# PowerShield.net
KiCad netlist of a schematic drawn in EAGLE
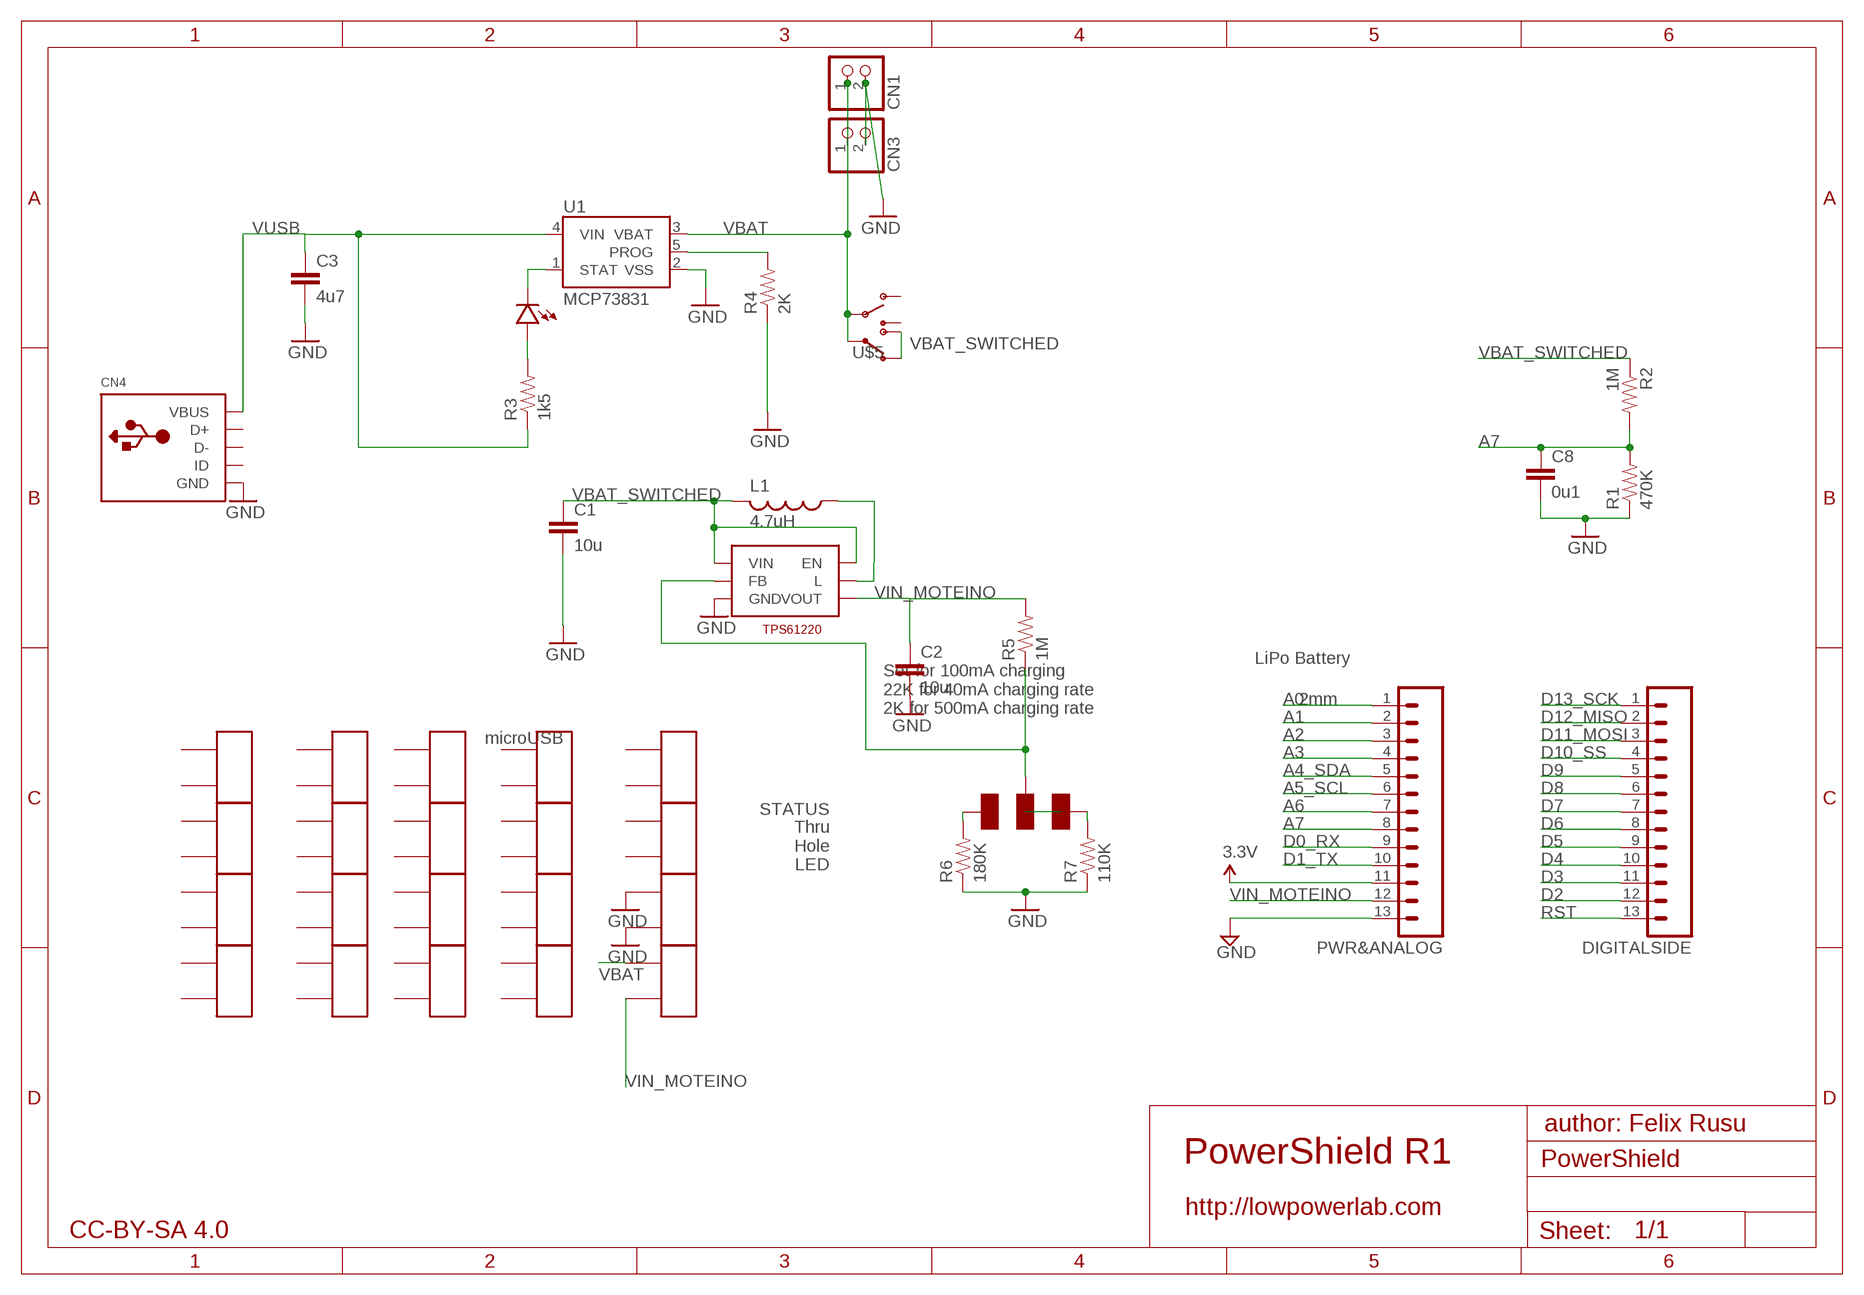
[diagram p0: schematic, sheet 1]

(export (version "E")
  (design (tool "Eeschema 10.0.6"))
  (components
    (comp (ref "C1")
      (value "10u")
      (footprint "eagle-import:0805-CAP-LARGEPADS")
      (libsource (lib "eagle-import") (part "CAP0805-CAP-LARGEPADS"))
    )
    (comp (ref "C2")
      (value "10u")
      (footprint "eagle-import:0805-CAP-LARGEPADS")
      (libsource (lib "eagle-import") (part "CAP0805-CAP-LARGEPADS"))
    )
    (comp (ref "C3")
      (value "4u7")
      (footprint "eagle-import:0603-CAP")
      (libsource (lib "eagle-import") (part "SparkFun_CAP0603-CAP"))
    )
    (comp (ref "C8")
      (value "0u1")
      (footprint "eagle-import:0603-CAP")
      (libsource (lib "eagle-import") (part "CAP0603-CAP"))
    )
    (comp (ref "CN1")
      (value "JST_2PIN-THM-RA")
      (footprint "eagle-import:JST-PH-2-THM-RA")
      (libsource (lib "eagle-import") (part "JST_2PIN-THM-RA"))
    )
    (comp (ref "CN3")
      (value "JST_2PIN-SMT-RA")
      (footprint "eagle-import:JST-PH-2-SMT-RA")
      (libsource (lib "eagle-import") (part "JST_2PIN-SMT-RA"))
    )
    (comp (ref "CN4")
      (value "USBMINIB")
      (footprint "eagle-import:USB-MINIB")
      (libsource (lib "eagle-import") (part "USBMINIB"))
    )
    (comp (ref "DIGITALSIDE")
      (value "HDR_13PINREGULAR")
      (footprint "eagle-import:1X13")
      (libsource (lib "eagle-import") (part "HDR_13PINREGULAR"))
    )
    (comp (ref "L1")
      (value "4.7uH")
      (footprint "eagle-import:INDUCTOR_NR3015")
      (libsource (lib "eagle-import") (part "INDUCTOR_NR3015"))
    )
    (comp (ref "PWR&ANALOG")
      (value "HDR_13PINREGULAR")
      (footprint "eagle-import:1X13")
      (libsource (lib "eagle-import") (part "HDR_13PINREGULAR"))
    )
    (comp (ref "R1")
      (value "470K")
      (footprint "eagle-import:0603-RES")
      (libsource (lib "eagle-import") (part "RESISTOR0603-RES"))
    )
    (comp (ref "R2")
      (value "1M")
      (footprint "eagle-import:0603-RES")
      (libsource (lib "eagle-import") (part "RESISTOR0603-RES"))
    )
    (comp (ref "R3")
      (value "1k5")
      (footprint "eagle-import:0603-RES")
      (libsource (lib "eagle-import") (part "RESISTOR0603-RES"))
    )
    (comp (ref "R4")
      (value "2K")
      (footprint "eagle-import:0603-RES")
      (libsource (lib "eagle-import") (part "RESISTOR0603-RES"))
    )
    (comp (ref "R5")
      (value "1M")
      (footprint "eagle-import:0603-RES")
      (libsource (lib "eagle-import") (part "RESISTOR0603-RES"))
    )
    (comp (ref "R6")
      (value "180K")
      (footprint "eagle-import:0603-RES")
      (libsource (lib "eagle-import") (part "RESISTOR0603-RES"))
    )
    (comp (ref "R7")
      (value "110K")
      (footprint "eagle-import:0603-RES")
      (libsource (lib "eagle-import") (part "RESISTOR0603-RES"))
    )
    (comp (ref "U$1")
      (value "SWITCH_SPDT")
      (footprint "eagle-import:SWITCH-SPDT")
      (libsource (lib "eagle-import") (part "SWITCH_SPDT"))
    )
    (comp (ref "U$2")
      (value "TPS61222SOT363")
      (footprint "eagle-import:SOT363")
      (libsource (lib "eagle-import") (part "TPS61222SOT363"))
    )
    (comp (ref "U$4")
      (value "LED0603")
      (footprint "eagle-import:0603-LED")
      (libsource (lib "eagle-import") (part "LED0603"))
    )
    (comp (ref "U$5")
      (value "SWITCH_SPDT")
      (footprint "eagle-import:KPS-1290")
      (libsource (lib "eagle-import") (part "SparkFun-Electromechanical_SWITCH_SPDT"))
    )
    (comp (ref "U$6")
      (value "HDR_2PIN")
      (footprint "eagle-import:1X02_NS")
      (libsource (lib "eagle-import") (part "HDR_2PIN"))
    )
    (comp (ref "U$7")
      (value "HDR_2PIN")
      (footprint "eagle-import:1X02_NS")
      (libsource (lib "eagle-import") (part "HDR_2PIN"))
    )
    (comp (ref "U$8")
      (value "HDR_2PIN")
      (footprint "eagle-import:1X02_NS")
      (libsource (lib "eagle-import") (part "HDR_2PIN"))
    )
    (comp (ref "U$9")
      (value "HDR_2PIN")
      (footprint "eagle-import:1X02_NS")
      (libsource (lib "eagle-import") (part "HDR_2PIN"))
    )
    (comp (ref "U$10")
      (value "HDR_2PIN")
      (footprint "eagle-import:1X02_NS")
      (libsource (lib "eagle-import") (part "HDR_2PIN"))
    )
    (comp (ref "U$11")
      (value "HDR_2PIN")
      (footprint "eagle-import:1X02_NS")
      (libsource (lib "eagle-import") (part "HDR_2PIN"))
    )
    (comp (ref "U$12")
      (value "HDR_2PIN")
      (footprint "eagle-import:1X02_NS")
      (libsource (lib "eagle-import") (part "HDR_2PIN"))
    )
    (comp (ref "U$13")
      (value "HDR_2PIN")
      (footprint "eagle-import:1X02_NS")
      (libsource (lib "eagle-import") (part "HDR_2PIN"))
    )
    (comp (ref "U$14")
      (value "HDR_2PIN")
      (footprint "eagle-import:1X02_NS")
      (libsource (lib "eagle-import") (part "HDR_2PIN"))
    )
    (comp (ref "U$15")
      (value "HDR_2PIN")
      (footprint "eagle-import:1X02_NS")
      (libsource (lib "eagle-import") (part "HDR_2PIN"))
    )
    (comp (ref "U$16")
      (value "HDR_2PIN")
      (footprint "eagle-import:1X02_NS")
      (libsource (lib "eagle-import") (part "HDR_2PIN"))
    )
    (comp (ref "U$17")
      (value "HDR_2PIN")
      (footprint "eagle-import:1X02_NS")
      (libsource (lib "eagle-import") (part "HDR_2PIN"))
    )
    (comp (ref "U$18")
      (value "HDR_2PIN")
      (footprint "eagle-import:1X02_NS")
      (libsource (lib "eagle-import") (part "HDR_2PIN"))
    )
    (comp (ref "U$19")
      (value "HDR_2PIN")
      (footprint "eagle-import:1X02_NS")
      (libsource (lib "eagle-import") (part "HDR_2PIN"))
    )
    (comp (ref "U$20")
      (value "HDR_2PIN")
      (footprint "eagle-import:1X02_NS")
      (libsource (lib "eagle-import") (part "HDR_2PIN"))
    )
    (comp (ref "U$21")
      (value "HDR_2PIN")
      (footprint "eagle-import:1X02_NS")
      (libsource (lib "eagle-import") (part "HDR_2PIN"))
    )
    (comp (ref "U$22")
      (value "HDR_2PIN")
      (footprint "eagle-import:1X02_NS")
      (libsource (lib "eagle-import") (part "HDR_2PIN"))
    )
    (comp (ref "U$23")
      (value "HDR_2PIN")
      (footprint "eagle-import:1X02_NS")
      (libsource (lib "eagle-import") (part "HDR_2PIN"))
    )
    (comp (ref "U$24")
      (value "HDR_2PIN")
      (footprint "eagle-import:1X02_NS")
      (libsource (lib "eagle-import") (part "HDR_2PIN"))
    )
    (comp (ref "U$25")
      (value "HDR_2PIN")
      (footprint "eagle-import:1X02_NS")
      (libsource (lib "eagle-import") (part "HDR_2PIN"))
    )
    (comp (ref "U$26")
      (value "JUMPER_3")
      (footprint "eagle-import:JUMPER_3")
      (libsource (lib "eagle-import") (part "JUMPER_3"))
    )
    (comp (ref "U1")
      (value "MCP73831")
      (footprint "eagle-import:SOT23-5")
      (libsource (lib "eagle-import") (part "MCP73831"))
    )
  )
  (nets
    (net (code "1") (name "/A0") (class "Default")
      (node (ref "PWR&ANALOG") (pin "1") (pinfunction "1_1") (pintype "passive"))
    )
    (net (code "2") (name "/A1") (class "Default")
      (node (ref "PWR&ANALOG") (pin "2") (pinfunction "2_2") (pintype "passive"))
    )
    (net (code "3") (name "/A2") (class "Default")
      (node (ref "PWR&ANALOG") (pin "3") (pinfunction "3_3") (pintype "passive"))
    )
    (net (code "4") (name "/A3") (class "Default")
      (node (ref "PWR&ANALOG") (pin "4") (pinfunction "4_4") (pintype "passive"))
    )
    (net (code "5") (name "/A4_SDA") (class "Default")
      (node (ref "PWR&ANALOG") (pin "5") (pinfunction "5_5") (pintype "passive"))
    )
    (net (code "6") (name "/A5_SCL") (class "Default")
      (node (ref "PWR&ANALOG") (pin "6") (pinfunction "6_6") (pintype "passive"))
    )
    (net (code "7") (name "/A6") (class "Default")
      (node (ref "PWR&ANALOG") (pin "7") (pinfunction "7_7") (pintype "passive"))
    )
    (net (code "8") (name "/A7") (class "Default")
      (node (ref "C8") (pin "1") (pinfunction "1_1") (pintype "passive"))
      (node (ref "PWR&ANALOG") (pin "8") (pinfunction "8_8") (pintype "passive"))
      (node (ref "R1") (pin "2") (pinfunction "2_2") (pintype "passive"))
      (node (ref "R2") (pin "2") (pinfunction "2_2") (pintype "passive"))
    )
    (net (code "9") (name "/D0_RX") (class "Default")
      (node (ref "PWR&ANALOG") (pin "9") (pinfunction "9_9") (pintype "passive"))
    )
    (net (code "10") (name "/D1_TX") (class "Default")
      (node (ref "PWR&ANALOG") (pin "10") (pinfunction "10_10") (pintype "passive"))
    )
    (net (code "11") (name "/D2") (class "Default")
      (node (ref "DIGITALSIDE") (pin "12") (pinfunction "12_12") (pintype "passive"))
    )
    (net (code "12") (name "/D3") (class "Default")
      (node (ref "DIGITALSIDE") (pin "11") (pinfunction "11_11") (pintype "passive"))
    )
    (net (code "13") (name "/D4") (class "Default")
      (node (ref "DIGITALSIDE") (pin "10") (pinfunction "10_10") (pintype "passive"))
    )
    (net (code "14") (name "/D5") (class "Default")
      (node (ref "DIGITALSIDE") (pin "9") (pinfunction "9_9") (pintype "passive"))
    )
    (net (code "15") (name "/D6") (class "Default")
      (node (ref "DIGITALSIDE") (pin "8") (pinfunction "8_8") (pintype "passive"))
    )
    (net (code "16") (name "/D7") (class "Default")
      (node (ref "DIGITALSIDE") (pin "7") (pinfunction "7_7") (pintype "passive"))
    )
    (net (code "17") (name "/D8") (class "Default")
      (node (ref "DIGITALSIDE") (pin "6") (pinfunction "6_6") (pintype "passive"))
    )
    (net (code "18") (name "/D9") (class "Default")
      (node (ref "DIGITALSIDE") (pin "5") (pinfunction "5_5") (pintype "passive"))
    )
    (net (code "19") (name "/D10_SS") (class "Default")
      (node (ref "DIGITALSIDE") (pin "4") (pinfunction "4_4") (pintype "passive"))
    )
    (net (code "20") (name "/D11_MOSI") (class "Default")
      (node (ref "DIGITALSIDE") (pin "3") (pinfunction "3_3") (pintype "passive"))
    )
    (net (code "21") (name "/D12_MISO") (class "Default")
      (node (ref "DIGITALSIDE") (pin "2") (pinfunction "2_2") (pintype "passive"))
    )
    (net (code "22") (name "/D13_SCK") (class "Default")
      (node (ref "DIGITALSIDE") (pin "1") (pinfunction "1_1") (pintype "passive"))
    )
    (net (code "23") (name "/RST") (class "Default")
      (node (ref "DIGITALSIDE") (pin "13") (pinfunction "13_13") (pintype "passive"))
    )
    (net (code "24") (name "/VBAT") (class "Default")
      (node (ref "CN1") (pin "1") (pinfunction "2_1") (pintype "passive"))
      (node (ref "CN3") (pin "1") (pinfunction "2_1") (pintype "passive"))
      (node (ref "U$1") (pin "2") (pinfunction "2_2") (pintype "bidirectional"))
      (node (ref "U$25") (pin "1") (pinfunction "P$1_1") (pintype "bidirectional"))
      (node (ref "U$5") (pin "P") (pinfunction "P_P") (pintype "passive"))
      (node (ref "U1") (pin "3") (pinfunction "VBAT_3") (pintype "power_in"))
    )
    (net (code "25") (name "/VBAT_SWITCHED") (class "Default")
      (node (ref "C1") (pin "1") (pinfunction "1_1") (pintype "passive"))
      (node (ref "L1") (pin "P$2") (pinfunction "2_P$2") (pintype "passive"))
      (node (ref "R2") (pin "1") (pinfunction "1_1") (pintype "passive"))
      (node (ref "U$1") (pin "1") (pinfunction "1_1") (pintype "bidirectional"))
      (node (ref "U$2") (pin "1") (pinfunction "VIN_1") (pintype "bidirectional"))
      (node (ref "U$2") (pin "6") (pinfunction "EN_6") (pintype "bidirectional"))
      (node (ref "U$5") (pin "S") (pinfunction "S_S") (pintype "passive"))
    )
    (net (code "26") (name "/VIN_MOTEINO") (class "Default")
      (node (ref "C2") (pin "1") (pinfunction "1_1") (pintype "passive"))
      (node (ref "PWR&ANALOG") (pin "12") (pinfunction "12_12") (pintype "passive"))
      (node (ref "R5") (pin "2") (pinfunction "2_2") (pintype "passive"))
      (node (ref "U$2") (pin "4") (pinfunction "VOUT_4") (pintype "bidirectional"))
      (node (ref "U$25") (pin "2") (pinfunction "P$2_2") (pintype "bidirectional"))
    )
    (net (code "27") (name "/VUSB") (class "Default")
      (node (ref "C3") (pin "1") (pinfunction "1_1") (pintype "passive"))
      (node (ref "CN4") (pin "VBUS") (pinfunction "VBUS_VBUS") (pintype "power_in"))
      (node (ref "R3") (pin "1") (pinfunction "1_1") (pintype "passive"))
      (node (ref "U1") (pin "4") (pinfunction "VIN_4") (pintype "power_in"))
    )
    (net (code "28") (name "3.3V") (class "Default")
      (node (ref "PWR&ANALOG") (pin "11") (pinfunction "11_11") (pintype "passive"))
    )
    (net (code "29") (name "GND") (class "Default")
      (node (ref "C1") (pin "2") (pinfunction "2_2") (pintype "passive"))
      (node (ref "C2") (pin "2") (pinfunction "2_2") (pintype "passive"))
      (node (ref "C3") (pin "2") (pinfunction "2_2") (pintype "passive"))
      (node (ref "C8") (pin "2") (pinfunction "2_2") (pintype "passive"))
      (node (ref "CN1") (pin "2") (pinfunction "1_2") (pintype "passive"))
      (node (ref "CN3") (pin "2") (pinfunction "1_2") (pintype "passive"))
      (node (ref "CN4") (pin "GND") (pinfunction "GND_GND") (pintype "power_in"))
      (node (ref "PWR&ANALOG") (pin "13") (pinfunction "13_13") (pintype "passive"))
      (node (ref "R1") (pin "1") (pinfunction "1_1") (pintype "passive"))
      (node (ref "R4") (pin "1") (pinfunction "1_1") (pintype "passive"))
      (node (ref "R6") (pin "1") (pinfunction "1_1") (pintype "passive"))
      (node (ref "R7") (pin "1") (pinfunction "1_1") (pintype "passive"))
      (node (ref "U$2") (pin "3") (pinfunction "GND_3") (pintype "bidirectional"))
      (node (ref "U$24") (pin "1") (pinfunction "P$1_1") (pintype "bidirectional"))
      (node (ref "U$24") (pin "2") (pinfunction "P$2_2") (pintype "bidirectional"))
      (node (ref "U1") (pin "2") (pinfunction "VSS_2") (pintype "power_in"))
    )
    (net (code "30") (name "Net-(L1-1)") (class "Default")
      (node (ref "L1") (pin "P$1") (pinfunction "1_P$1") (pintype "passive"))
      (node (ref "U$2") (pin "5") (pinfunction "L_5") (pintype "bidirectional"))
    )
    (net (code "31") (name "Net-(R3-Pad2)") (class "Default")
      (node (ref "R3") (pin "2") (pinfunction "2_2") (pintype "passive"))
      (node (ref "U$4") (pin "PLUS") (pinfunction "PLUS_PLUS") (pintype "passive"))
    )
    (net (code "32") (name "Net-(U$2-FB)") (class "Default")
      (node (ref "R5") (pin "1") (pinfunction "1_1") (pintype "passive"))
      (node (ref "U$2") (pin "2") (pinfunction "FB_2") (pintype "bidirectional"))
      (node (ref "U$26") (pin "2") (pinfunction "P$2_2") (pintype "bidirectional"))
    )
    (net (code "33") (name "Net-(U$26-P$1)") (class "Default")
      (node (ref "R7") (pin "2") (pinfunction "2_2") (pintype "passive"))
      (node (ref "U$26") (pin "1") (pinfunction "P$1_1") (pintype "bidirectional"))
    )
    (net (code "34") (name "Net-(U$26-P$3)") (class "Default")
      (node (ref "R6") (pin "2") (pinfunction "2_2") (pintype "passive"))
      (node (ref "U$26") (pin "3") (pinfunction "P$3_3") (pintype "bidirectional"))
    )
    (net (code "35") (name "Net-(U1-PROG)") (class "Default")
      (node (ref "R4") (pin "2") (pinfunction "2_2") (pintype "passive"))
      (node (ref "U1") (pin "5") (pinfunction "PROG_5") (pintype "input"))
    )
    (net (code "36") (name "Net-(U1-STAT)") (class "Default")
      (node (ref "U$4") (pin "MINUS") (pinfunction "MINUS_MINUS") (pintype "passive"))
      (node (ref "U1") (pin "1") (pinfunction "STAT_1") (pintype "output"))
    )
    (net (code "37") (name "unconnected-(CN4-PadD+)") (class "Default")
      (node (ref "CN4") (pin "D+") (pinfunction "D+_D+") (pintype "bidirectional"))
    )
    (net (code "38") (name "unconnected-(CN4-PadD-)") (class "Default")
      (node (ref "CN4") (pin "D-") (pinfunction "D-_D-") (pintype "bidirectional"))
    )
    (net (code "39") (name "unconnected-(CN4-PadID)") (class "Default")
      (node (ref "CN4") (pin "ID") (pinfunction "ID_ID") (pintype "bidirectional"))
    )
    (net (code "40") (name "unconnected-(U$1-Pad3)") (class "Default")
      (node (ref "U$1") (pin "3") (pinfunction "3_3") (pintype "bidirectional"))
    )
    (net (code "41") (name "unconnected-(U$5-PadO)") (class "Default")
      (node (ref "U$5") (pin "O") (pinfunction "O_O") (pintype "passive"))
    )
    (net (code "42") (name "unconnected-(U$6-P$1-Pad1)") (class "Default")
      (node (ref "U$6") (pin "1") (pinfunction "P$1_1") (pintype "bidirectional"))
    )
    (net (code "43") (name "unconnected-(U$6-P$2-Pad2)") (class "Default")
      (node (ref "U$6") (pin "2") (pinfunction "P$2_2") (pintype "bidirectional"))
    )
    (net (code "44") (name "unconnected-(U$7-P$1-Pad1)") (class "Default")
      (node (ref "U$7") (pin "1") (pinfunction "P$1_1") (pintype "bidirectional"))
    )
    (net (code "45") (name "unconnected-(U$7-P$2-Pad2)") (class "Default")
      (node (ref "U$7") (pin "2") (pinfunction "P$2_2") (pintype "bidirectional"))
    )
    (net (code "46") (name "unconnected-(U$8-P$1-Pad1)") (class "Default")
      (node (ref "U$8") (pin "1") (pinfunction "P$1_1") (pintype "bidirectional"))
    )
    (net (code "47") (name "unconnected-(U$8-P$2-Pad2)") (class "Default")
      (node (ref "U$8") (pin "2") (pinfunction "P$2_2") (pintype "bidirectional"))
    )
    (net (code "48") (name "unconnected-(U$9-P$1-Pad1)") (class "Default")
      (node (ref "U$9") (pin "1") (pinfunction "P$1_1") (pintype "bidirectional"))
    )
    (net (code "49") (name "unconnected-(U$9-P$2-Pad2)") (class "Default")
      (node (ref "U$9") (pin "2") (pinfunction "P$2_2") (pintype "bidirectional"))
    )
    (net (code "50") (name "unconnected-(U$10-P$1-Pad1)") (class "Default")
      (node (ref "U$10") (pin "1") (pinfunction "P$1_1") (pintype "bidirectional"))
    )
    (net (code "51") (name "unconnected-(U$10-P$2-Pad2)") (class "Default")
      (node (ref "U$10") (pin "2") (pinfunction "P$2_2") (pintype "bidirectional"))
    )
    (net (code "52") (name "unconnected-(U$11-P$1-Pad1)") (class "Default")
      (node (ref "U$11") (pin "1") (pinfunction "P$1_1") (pintype "bidirectional"))
    )
    (net (code "53") (name "unconnected-(U$11-P$2-Pad2)") (class "Default")
      (node (ref "U$11") (pin "2") (pinfunction "P$2_2") (pintype "bidirectional"))
    )
    (net (code "54") (name "unconnected-(U$12-P$1-Pad1)") (class "Default")
      (node (ref "U$12") (pin "1") (pinfunction "P$1_1") (pintype "bidirectional"))
    )
    (net (code "55") (name "unconnected-(U$12-P$2-Pad2)") (class "Default")
      (node (ref "U$12") (pin "2") (pinfunction "P$2_2") (pintype "bidirectional"))
    )
    (net (code "56") (name "unconnected-(U$13-P$1-Pad1)") (class "Default")
      (node (ref "U$13") (pin "1") (pinfunction "P$1_1") (pintype "bidirectional"))
    )
    (net (code "57") (name "unconnected-(U$13-P$2-Pad2)") (class "Default")
      (node (ref "U$13") (pin "2") (pinfunction "P$2_2") (pintype "bidirectional"))
    )
    (net (code "58") (name "unconnected-(U$14-P$1-Pad1)") (class "Default")
      (node (ref "U$14") (pin "1") (pinfunction "P$1_1") (pintype "bidirectional"))
    )
    (net (code "59") (name "unconnected-(U$14-P$2-Pad2)") (class "Default")
      (node (ref "U$14") (pin "2") (pinfunction "P$2_2") (pintype "bidirectional"))
    )
    (net (code "60") (name "unconnected-(U$15-P$1-Pad1)") (class "Default")
      (node (ref "U$15") (pin "1") (pinfunction "P$1_1") (pintype "bidirectional"))
    )
    (net (code "61") (name "unconnected-(U$15-P$2-Pad2)") (class "Default")
      (node (ref "U$15") (pin "2") (pinfunction "P$2_2") (pintype "bidirectional"))
    )
    (net (code "62") (name "unconnected-(U$16-P$1-Pad1)") (class "Default")
      (node (ref "U$16") (pin "1") (pinfunction "P$1_1") (pintype "bidirectional"))
    )
    (net (code "63") (name "unconnected-(U$16-P$2-Pad2)") (class "Default")
      (node (ref "U$16") (pin "2") (pinfunction "P$2_2") (pintype "bidirectional"))
    )
    (net (code "64") (name "unconnected-(U$17-P$1-Pad1)") (class "Default")
      (node (ref "U$17") (pin "1") (pinfunction "P$1_1") (pintype "bidirectional"))
    )
    (net (code "65") (name "unconnected-(U$17-P$2-Pad2)") (class "Default")
      (node (ref "U$17") (pin "2") (pinfunction "P$2_2") (pintype "bidirectional"))
    )
    (net (code "66") (name "unconnected-(U$18-P$1-Pad1)") (class "Default")
      (node (ref "U$18") (pin "1") (pinfunction "P$1_1") (pintype "bidirectional"))
    )
    (net (code "67") (name "unconnected-(U$18-P$2-Pad2)") (class "Default")
      (node (ref "U$18") (pin "2") (pinfunction "P$2_2") (pintype "bidirectional"))
    )
    (net (code "68") (name "unconnected-(U$19-P$1-Pad1)") (class "Default")
      (node (ref "U$19") (pin "1") (pinfunction "P$1_1") (pintype "bidirectional"))
    )
    (net (code "69") (name "unconnected-(U$19-P$2-Pad2)") (class "Default")
      (node (ref "U$19") (pin "2") (pinfunction "P$2_2") (pintype "bidirectional"))
    )
    (net (code "70") (name "unconnected-(U$20-P$1-Pad1)") (class "Default")
      (node (ref "U$20") (pin "1") (pinfunction "P$1_1") (pintype "bidirectional"))
    )
    (net (code "71") (name "unconnected-(U$20-P$2-Pad2)") (class "Default")
      (node (ref "U$20") (pin "2") (pinfunction "P$2_2") (pintype "bidirectional"))
    )
    (net (code "72") (name "unconnected-(U$21-P$1-Pad1)") (class "Default")
      (node (ref "U$21") (pin "1") (pinfunction "P$1_1") (pintype "bidirectional"))
    )
    (net (code "73") (name "unconnected-(U$21-P$2-Pad2)") (class "Default")
      (node (ref "U$21") (pin "2") (pinfunction "P$2_2") (pintype "bidirectional"))
    )
    (net (code "74") (name "unconnected-(U$22-P$1-Pad1)") (class "Default")
      (node (ref "U$22") (pin "1") (pinfunction "P$1_1") (pintype "bidirectional"))
    )
    (net (code "75") (name "unconnected-(U$22-P$2-Pad2)") (class "Default")
      (node (ref "U$22") (pin "2") (pinfunction "P$2_2") (pintype "bidirectional"))
    )
    (net (code "76") (name "unconnected-(U$23-P$1-Pad1)") (class "Default")
      (node (ref "U$23") (pin "1") (pinfunction "P$1_1") (pintype "bidirectional"))
    )
    (net (code "77") (name "unconnected-(U$23-P$2-Pad2)") (class "Default")
      (node (ref "U$23") (pin "2") (pinfunction "P$2_2") (pintype "bidirectional"))
    )
  )
)
